# Connector_0_V1_01.net
KiCad netlist of a schematic drawn in Altium Designer
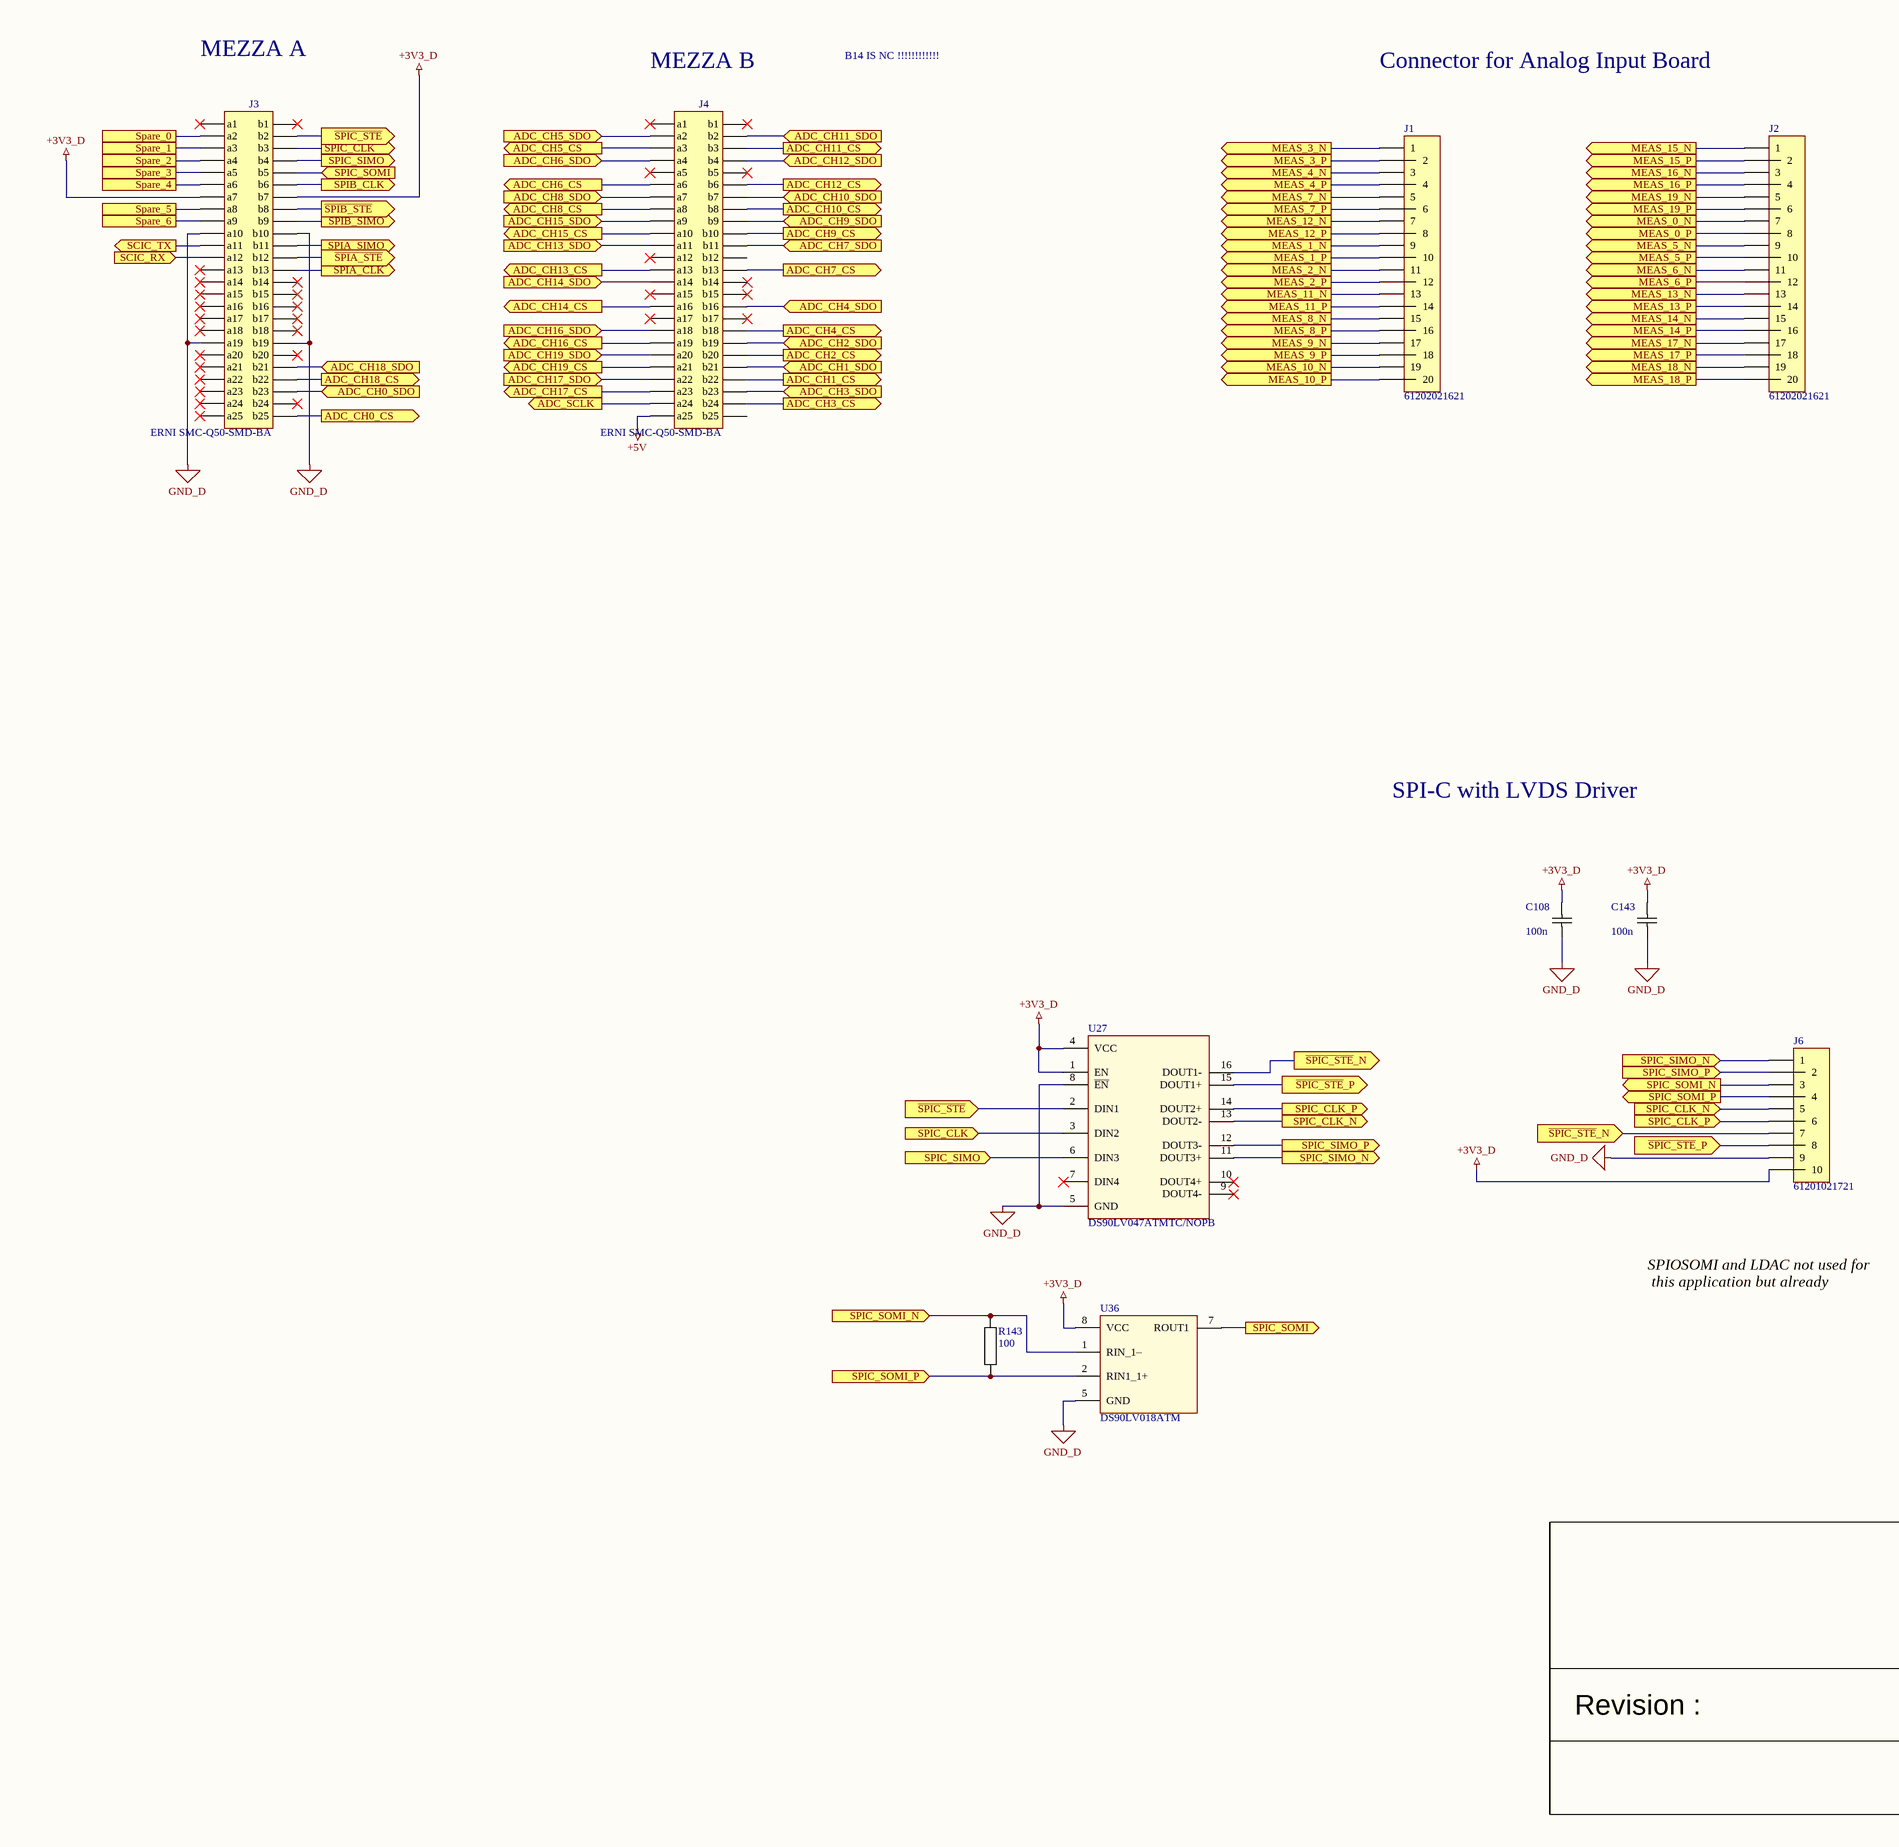
[diagram p0: Connector_0_V1_01.SchDoc, left]
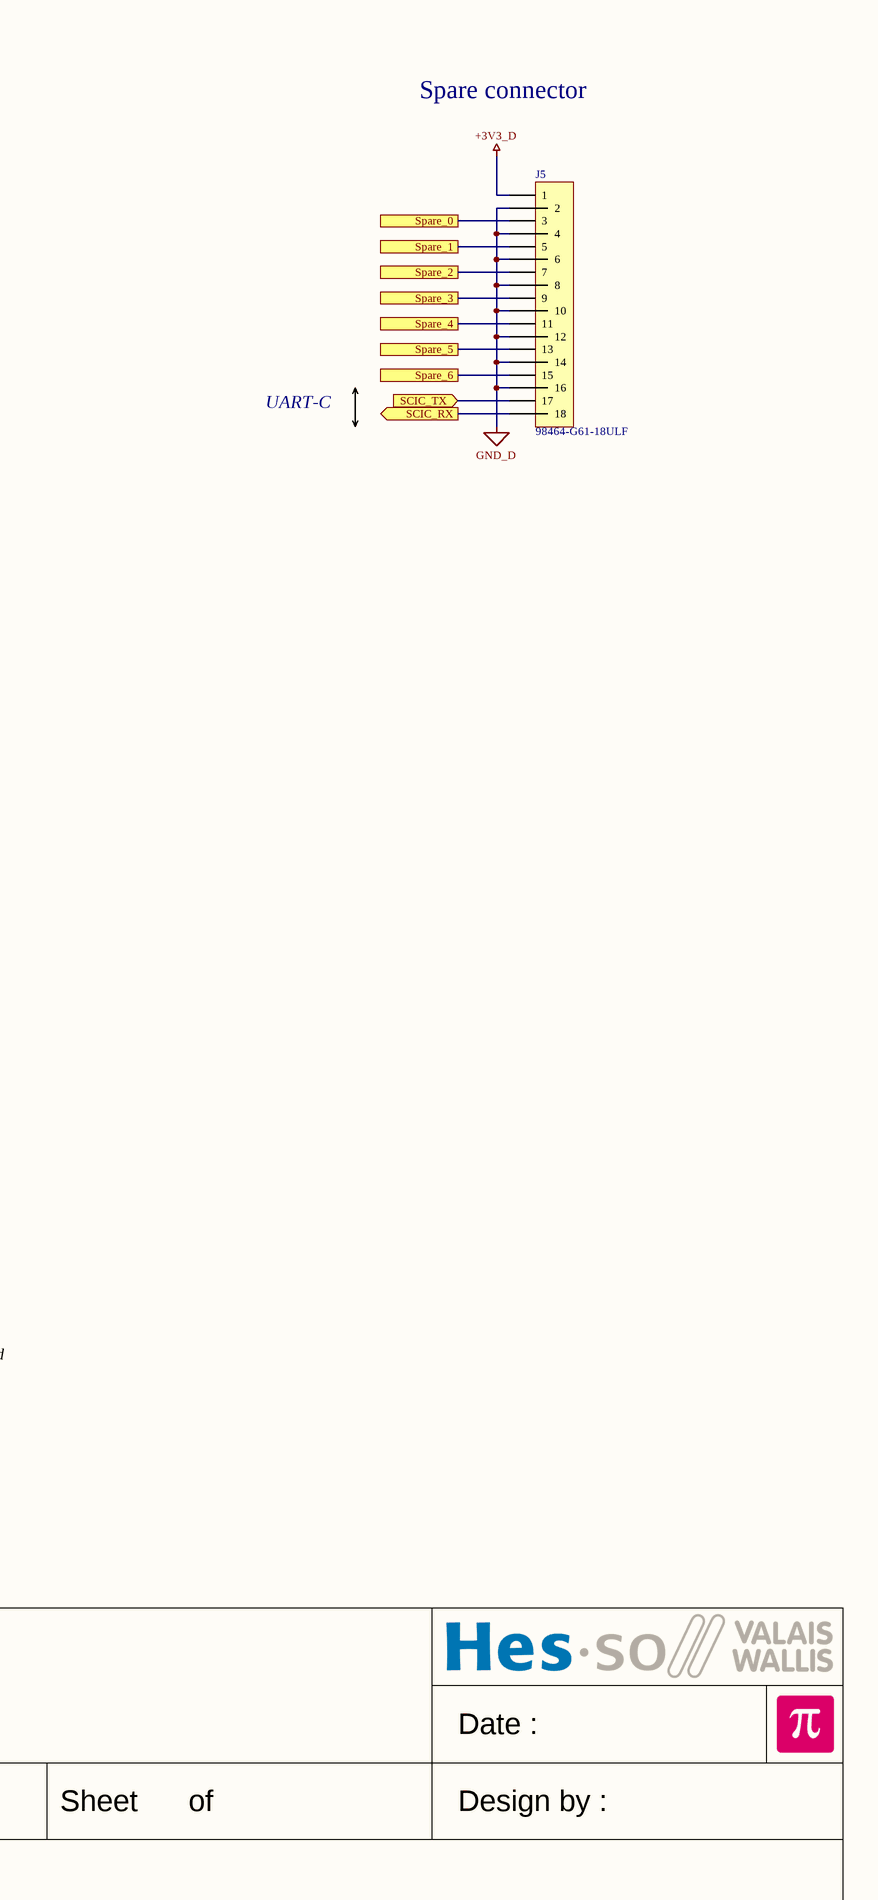
[diagram p1: Connector_0_V1_01.SchDoc, right]

(export (version "E")
  (design (tool "Eeschema 10.0.6"))
  (components
    (comp (ref "C108")
      (value "100n")
      (footprint "CAPACITOR 2012 REFLOW")
      (description "Capacitor X7R 10% 50V 2012(0805)")
      (libsource (lib "Capacitor") (part "Capacitor"))
    )
    (comp (ref "C143")
      (value "100n")
      (footprint "CAPACITOR 2012 REFLOW")
      (description "Capacitor X7R 10% 50V 2012(0805)")
      (libsource (lib "Capacitor") (part "Capacitor"))
    )
    (comp (ref "J1")
      (value "61202021621")
      (footprint "FlatCable2x10 2.54MM RIGHT ANGLE TH")
      (description "FlatCable2x10")
      (fields (field (name "MANUFACTURER") "Wurth Elektronik"))
      (libsource (lib "Connector") (part "FlatCable2x10"))
    )
    (comp (ref "J2")
      (value "61202021621")
      (footprint "FlatCable2x10 2.54MM RIGHT ANGLE TH")
      (description "FlatCable2x10")
      (fields (field (name "MANUFACTURER") "Wurth Elektronik"))
      (libsource (lib "Connector") (part "FlatCable2x10"))
    )
    (comp (ref "J3")
      (value "ERNI SMC-Q50-SMD-BA")
      (footprint "ERNI SMC-Q50-SMD-BA")
      (description "Male 1.27 pitch 2x25 pin connector")
      (libsource (lib "Connector") (part "ERNI SMC-Q50-SMD-BA"))
    )
    (comp (ref "J4")
      (value "ERNI SMC-Q50-SMD-BA")
      (footprint "ERNI SMC-Q50-SMD-BA")
      (description "Male 1.27 pitch 2x25 pin connector")
      (libsource (lib "Connector") (part "ERNI SMC-Q50-SMD-BA"))
    )
    (comp (ref "J5")
      (value "98464-G61-18ULF")
      (footprint "FlatCable2x9 2MM Straight SMD FCI 98414-G52-18ALF")
      (description "FlatCable2x9")
      (fields (field (name "MANUFACTURER") "Amphenol FCI"))
      (libsource (lib "Connector") (part "FlatCable2x9"))
    )
    (comp (ref "J6")
      (value "61201021721")
      (footprint "FlatCable2x5 2.54MM Straight TH")
      (description "FlatCable2x5")
      (fields (field (name "MANUFACTURER") "Wurth Elektronik"))
      (libsource (lib "Connector") (part "FlatCable2x5"))
    )
    (comp (ref "R143")
      (value "100")
      (footprint "RESISTOR 1608 REFLOW")
      (description "Resistor 1% 50V 100mW 1608(0603)")
      (libsource (lib "Resistor") (part "Resistor"))
    )
    (comp (ref "U27")
      (value "DS90LV047ATMTC/NOPB")
      (footprint "TSSOP16 P0.65 C5.0x4.5 H1.1")
      (description "DS90LV047A 3-V LVDS Quad CMOS Differential Line Driver")
      (fields (field (name "MANUFACTURER") "Texas Instruments"))
      (libsource (lib "IntegratedCircuit") (part "DS90LV047A"))
    )
    (comp (ref "U36")
      (value "DS90LV018ATM")
      (footprint "SO8 P1.27 C4.0X5.0 H1.75")
      (description "3-V LVDS single CMOS differential line receiver")
      (libsource (lib "IntegratedCircuit") (part "DS90LV018ATM"))
    )
  )
  (nets
    (net (code "1") (name "+3V3_D") (class "Default")
      (node (ref "C108") (pin "2") (pinfunction "2_2") (pintype "passive"))
      (node (ref "C143") (pin "2") (pinfunction "2_2") (pintype "passive"))
      (node (ref "J3") (pin "a7") (pinfunction "a7_a7") (pintype "passive"))
      (node (ref "J3") (pin "b7") (pinfunction "b7_b7") (pintype "passive"))
      (node (ref "J5") (pin "1") (pinfunction "1_1") (pintype "passive"))
      (node (ref "J6") (pin "10") (pinfunction "10_10") (pintype "passive"))
      (node (ref "U27") (pin "1") (pinfunction "EN_1") (pintype "passive"))
      (node (ref "U27") (pin "4") (pinfunction "VCC_4") (pintype "passive"))
      (node (ref "U36") (pin "8") (pinfunction "VCC_8") (pintype "passive"))
    )
    (net (code "2") (name "+5V") (class "Default")
      (node (ref "J4") (pin "a25") (pinfunction "a25_a25") (pintype "passive"))
    )
    (net (code "3") (name "/ADC_CH0_CS") (class "Default")
      (node (ref "J3") (pin "b25") (pinfunction "b25_b25") (pintype "passive"))
    )
    (net (code "4") (name "/ADC_CH0_SDO") (class "Default")
      (node (ref "J3") (pin "b23") (pinfunction "b23_b23") (pintype "passive"))
    )
    (net (code "5") (name "/ADC_CH1_CS") (class "Default")
      (node (ref "J4") (pin "b22") (pinfunction "b22_b22") (pintype "passive"))
    )
    (net (code "6") (name "/ADC_CH1_SDO") (class "Default")
      (node (ref "J4") (pin "b21") (pinfunction "b21_b21") (pintype "passive"))
    )
    (net (code "7") (name "/ADC_CH2_CS") (class "Default")
      (node (ref "J4") (pin "b20") (pinfunction "b20_b20") (pintype "passive"))
    )
    (net (code "8") (name "/ADC_CH2_SDO") (class "Default")
      (node (ref "J4") (pin "b19") (pinfunction "b19_b19") (pintype "passive"))
    )
    (net (code "9") (name "/ADC_CH3_CS") (class "Default")
      (node (ref "J4") (pin "b24") (pinfunction "b24_b24") (pintype "passive"))
    )
    (net (code "10") (name "/ADC_CH3_SDO") (class "Default")
      (node (ref "J4") (pin "b23") (pinfunction "b23_b23") (pintype "passive"))
    )
    (net (code "11") (name "/ADC_CH4_CS") (class "Default")
      (node (ref "J4") (pin "b18") (pinfunction "b18_b18") (pintype "passive"))
    )
    (net (code "12") (name "/ADC_CH4_SDO") (class "Default")
      (node (ref "J4") (pin "b16") (pinfunction "b16_b16") (pintype "passive"))
    )
    (net (code "13") (name "/ADC_CH5_CS") (class "Default")
      (node (ref "J4") (pin "a3") (pinfunction "a3_a3") (pintype "passive"))
    )
    (net (code "14") (name "/ADC_CH5_SDO") (class "Default")
      (node (ref "J4") (pin "a2") (pinfunction "a2_a2") (pintype "passive"))
    )
    (net (code "15") (name "/ADC_CH6_CS") (class "Default")
      (node (ref "J4") (pin "a6") (pinfunction "a6_a6") (pintype "passive"))
    )
    (net (code "16") (name "/ADC_CH6_SDO") (class "Default")
      (node (ref "J4") (pin "a4") (pinfunction "a4_a4") (pintype "passive"))
    )
    (net (code "17") (name "/ADC_CH7_CS") (class "Default")
      (node (ref "J4") (pin "b13") (pinfunction "b13_b13") (pintype "passive"))
    )
    (net (code "18") (name "/ADC_CH7_SDO") (class "Default")
      (node (ref "J4") (pin "b11") (pinfunction "b11_b11") (pintype "passive"))
    )
    (net (code "19") (name "/ADC_CH8_CS") (class "Default")
      (node (ref "J4") (pin "a8") (pinfunction "a8_a8") (pintype "passive"))
    )
    (net (code "20") (name "/ADC_CH8_SDO") (class "Default")
      (node (ref "J4") (pin "a7") (pinfunction "a7_a7") (pintype "passive"))
    )
    (net (code "21") (name "/ADC_CH9_CS") (class "Default")
      (node (ref "J4") (pin "b10") (pinfunction "b10_b10") (pintype "passive"))
    )
    (net (code "22") (name "/ADC_CH9_SDO") (class "Default")
      (node (ref "J4") (pin "b9") (pinfunction "b9_b9") (pintype "passive"))
    )
    (net (code "23") (name "/ADC_CH10_CS") (class "Default")
      (node (ref "J4") (pin "b8") (pinfunction "b8_b8") (pintype "passive"))
    )
    (net (code "24") (name "/ADC_CH10_SDO") (class "Default")
      (node (ref "J4") (pin "b7") (pinfunction "b7_b7") (pintype "passive"))
    )
    (net (code "25") (name "/ADC_CH11_CS") (class "Default")
      (node (ref "J4") (pin "b3") (pinfunction "b3_b3") (pintype "passive"))
    )
    (net (code "26") (name "/ADC_CH11_SDO") (class "Default")
      (node (ref "J4") (pin "b2") (pinfunction "b2_b2") (pintype "passive"))
    )
    (net (code "27") (name "/ADC_CH12_CS") (class "Default")
      (node (ref "J4") (pin "b6") (pinfunction "b6_b6") (pintype "passive"))
    )
    (net (code "28") (name "/ADC_CH12_SDO") (class "Default")
      (node (ref "J4") (pin "b4") (pinfunction "b4_b4") (pintype "passive"))
    )
    (net (code "29") (name "/ADC_CH13_CS") (class "Default")
      (node (ref "J4") (pin "a13") (pinfunction "a13_a13") (pintype "passive"))
    )
    (net (code "30") (name "/ADC_CH13_SDO") (class "Default")
      (node (ref "J4") (pin "a11") (pinfunction "a11_a11") (pintype "passive"))
    )
    (net (code "31") (name "/ADC_CH14_CS") (class "Default")
      (node (ref "J4") (pin "a16") (pinfunction "a16_a16") (pintype "passive"))
    )
    (net (code "32") (name "/ADC_CH14_SDO") (class "Default")
      (node (ref "J4") (pin "a14") (pinfunction "a14_a14") (pintype "passive"))
    )
    (net (code "33") (name "/ADC_CH15_CS") (class "Default")
      (node (ref "J4") (pin "a10") (pinfunction "a10_a10") (pintype "passive"))
    )
    (net (code "34") (name "/ADC_CH15_SDO") (class "Default")
      (node (ref "J4") (pin "a9") (pinfunction "a9_a9") (pintype "passive"))
    )
    (net (code "35") (name "/ADC_CH16_CS") (class "Default")
      (node (ref "J4") (pin "a19") (pinfunction "a19_a19") (pintype "passive"))
    )
    (net (code "36") (name "/ADC_CH16_SDO") (class "Default")
      (node (ref "J4") (pin "a18") (pinfunction "a18_a18") (pintype "passive"))
    )
    (net (code "37") (name "/ADC_CH17_CS") (class "Default")
      (node (ref "J4") (pin "a23") (pinfunction "a23_a23") (pintype "passive"))
    )
    (net (code "38") (name "/ADC_CH17_SDO") (class "Default")
      (node (ref "J4") (pin "a22") (pinfunction "a22_a22") (pintype "passive"))
    )
    (net (code "39") (name "/ADC_CH18_CS") (class "Default")
      (node (ref "J3") (pin "b22") (pinfunction "b22_b22") (pintype "passive"))
    )
    (net (code "40") (name "/ADC_CH18_SDO") (class "Default")
      (node (ref "J3") (pin "b21") (pinfunction "b21_b21") (pintype "passive"))
    )
    (net (code "41") (name "/ADC_CH19_CS") (class "Default")
      (node (ref "J4") (pin "a21") (pinfunction "a21_a21") (pintype "passive"))
    )
    (net (code "42") (name "/ADC_CH19_SDO") (class "Default")
      (node (ref "J4") (pin "a20") (pinfunction "a20_a20") (pintype "passive"))
    )
    (net (code "43") (name "/ADC_SCLK") (class "Default")
      (node (ref "J4") (pin "a24") (pinfunction "a24_a24") (pintype "passive"))
    )
    (net (code "44") (name "/MEAS_0_N") (class "Default")
      (node (ref "J2") (pin "7") (pinfunction "7_7") (pintype "passive"))
    )
    (net (code "45") (name "/MEAS_0_P") (class "Default")
      (node (ref "J2") (pin "8") (pinfunction "8_8") (pintype "passive"))
    )
    (net (code "46") (name "/MEAS_1_N") (class "Default")
      (node (ref "J1") (pin "9") (pinfunction "9_9") (pintype "passive"))
    )
    (net (code "47") (name "/MEAS_1_P") (class "Default")
      (node (ref "J1") (pin "10") (pinfunction "10_10") (pintype "passive"))
    )
    (net (code "48") (name "/MEAS_2_N") (class "Default")
      (node (ref "J1") (pin "11") (pinfunction "11_11") (pintype "passive"))
    )
    (net (code "49") (name "/MEAS_2_P") (class "Default")
      (node (ref "J1") (pin "12") (pinfunction "12_12") (pintype "passive"))
    )
    (net (code "50") (name "/MEAS_3_N") (class "Default")
      (node (ref "J1") (pin "1") (pinfunction "1_1") (pintype "passive"))
    )
    (net (code "51") (name "/MEAS_3_P") (class "Default")
      (node (ref "J1") (pin "2") (pinfunction "2_2") (pintype "passive"))
    )
    (net (code "52") (name "/MEAS_4_N") (class "Default")
      (node (ref "J1") (pin "3") (pinfunction "3_3") (pintype "passive"))
    )
    (net (code "53") (name "/MEAS_4_P") (class "Default")
      (node (ref "J1") (pin "4") (pinfunction "4_4") (pintype "passive"))
    )
    (net (code "54") (name "/MEAS_5_N") (class "Default")
      (node (ref "J2") (pin "9") (pinfunction "9_9") (pintype "passive"))
    )
    (net (code "55") (name "/MEAS_5_P") (class "Default")
      (node (ref "J2") (pin "10") (pinfunction "10_10") (pintype "passive"))
    )
    (net (code "56") (name "/MEAS_6_N") (class "Default")
      (node (ref "J2") (pin "11") (pinfunction "11_11") (pintype "passive"))
    )
    (net (code "57") (name "/MEAS_6_P") (class "Default")
      (node (ref "J2") (pin "12") (pinfunction "12_12") (pintype "passive"))
    )
    (net (code "58") (name "/MEAS_7_N") (class "Default")
      (node (ref "J1") (pin "5") (pinfunction "5_5") (pintype "passive"))
    )
    (net (code "59") (name "/MEAS_7_P") (class "Default")
      (node (ref "J1") (pin "6") (pinfunction "6_6") (pintype "passive"))
    )
    (net (code "60") (name "/MEAS_8_N") (class "Default")
      (node (ref "J1") (pin "15") (pinfunction "15_15") (pintype "passive"))
    )
    (net (code "61") (name "/MEAS_8_P") (class "Default")
      (node (ref "J1") (pin "16") (pinfunction "16_16") (pintype "passive"))
    )
    (net (code "62") (name "/MEAS_9_N") (class "Default")
      (node (ref "J1") (pin "17") (pinfunction "17_17") (pintype "passive"))
    )
    (net (code "63") (name "/MEAS_9_P") (class "Default")
      (node (ref "J1") (pin "18") (pinfunction "18_18") (pintype "passive"))
    )
    (net (code "64") (name "/MEAS_10_N") (class "Default")
      (node (ref "J1") (pin "19") (pinfunction "19_19") (pintype "passive"))
    )
    (net (code "65") (name "/MEAS_10_P") (class "Default")
      (node (ref "J1") (pin "20") (pinfunction "20_20") (pintype "passive"))
    )
    (net (code "66") (name "/MEAS_11_N") (class "Default")
      (node (ref "J1") (pin "13") (pinfunction "13_13") (pintype "passive"))
    )
    (net (code "67") (name "/MEAS_11_P") (class "Default")
      (node (ref "J1") (pin "14") (pinfunction "14_14") (pintype "passive"))
    )
    (net (code "68") (name "/MEAS_12_N") (class "Default")
      (node (ref "J1") (pin "7") (pinfunction "7_7") (pintype "passive"))
    )
    (net (code "69") (name "/MEAS_12_P") (class "Default")
      (node (ref "J1") (pin "8") (pinfunction "8_8") (pintype "passive"))
    )
    (net (code "70") (name "/MEAS_13_N") (class "Default")
      (node (ref "J2") (pin "13") (pinfunction "13_13") (pintype "passive"))
    )
    (net (code "71") (name "/MEAS_13_P") (class "Default")
      (node (ref "J2") (pin "14") (pinfunction "14_14") (pintype "passive"))
    )
    (net (code "72") (name "/MEAS_14_N") (class "Default")
      (node (ref "J2") (pin "15") (pinfunction "15_15") (pintype "passive"))
    )
    (net (code "73") (name "/MEAS_14_P") (class "Default")
      (node (ref "J2") (pin "16") (pinfunction "16_16") (pintype "passive"))
    )
    (net (code "74") (name "/MEAS_15_N") (class "Default")
      (node (ref "J2") (pin "1") (pinfunction "1_1") (pintype "passive"))
    )
    (net (code "75") (name "/MEAS_15_P") (class "Default")
      (node (ref "J2") (pin "2") (pinfunction "2_2") (pintype "passive"))
    )
    (net (code "76") (name "/MEAS_16_N") (class "Default")
      (node (ref "J2") (pin "3") (pinfunction "3_3") (pintype "passive"))
    )
    (net (code "77") (name "/MEAS_16_P") (class "Default")
      (node (ref "J2") (pin "4") (pinfunction "4_4") (pintype "passive"))
    )
    (net (code "78") (name "/MEAS_17_N") (class "Default")
      (node (ref "J2") (pin "17") (pinfunction "17_17") (pintype "passive"))
    )
    (net (code "79") (name "/MEAS_17_P") (class "Default")
      (node (ref "J2") (pin "18") (pinfunction "18_18") (pintype "passive"))
    )
    (net (code "80") (name "/MEAS_18_N") (class "Default")
      (node (ref "J2") (pin "19") (pinfunction "19_19") (pintype "passive"))
    )
    (net (code "81") (name "/MEAS_18_P") (class "Default")
      (node (ref "J2") (pin "20") (pinfunction "20_20") (pintype "passive"))
    )
    (net (code "82") (name "/MEAS_19_N") (class "Default")
      (node (ref "J2") (pin "5") (pinfunction "5_5") (pintype "passive"))
    )
    (net (code "83") (name "/MEAS_19_P") (class "Default")
      (node (ref "J2") (pin "6") (pinfunction "6_6") (pintype "passive"))
    )
    (net (code "84") (name "/SCIC_RX") (class "Default")
      (node (ref "J3") (pin "a12") (pinfunction "a12_a12") (pintype "passive"))
      (node (ref "J5") (pin "18") (pinfunction "18_18") (pintype "passive"))
    )
    (net (code "85") (name "/SCIC_TX") (class "Default")
      (node (ref "J3") (pin "a11") (pinfunction "a11_a11") (pintype "passive"))
      (node (ref "J5") (pin "17") (pinfunction "17_17") (pintype "passive"))
    )
    (net (code "86") (name "/SPIA_CLK") (class "Default")
      (node (ref "J3") (pin "b13") (pinfunction "b13_b13") (pintype "passive"))
    )
    (net (code "87") (name "/SPIA_SIMO") (class "Default")
      (node (ref "J3") (pin "b11") (pinfunction "b11_b11") (pintype "passive"))
    )
    (net (code "88") (name "/SPIB_CLK") (class "Default")
      (node (ref "J3") (pin "b6") (pinfunction "b6_b6") (pintype "passive"))
    )
    (net (code "89") (name "/SPIB_SIMO") (class "Default")
      (node (ref "J3") (pin "b9") (pinfunction "b9_b9") (pintype "passive"))
    )
    (net (code "90") (name "/SPIC_CLK") (class "Default")
      (node (ref "J3") (pin "b3") (pinfunction "b3_b3") (pintype "passive"))
      (node (ref "U27") (pin "3") (pinfunction "DIN2_3") (pintype "passive"))
    )
    (net (code "91") (name "/SPIC_CLK_N") (class "Default")
      (node (ref "J6") (pin "5") (pinfunction "5_5") (pintype "passive"))
      (node (ref "U27") (pin "13") (pinfunction "DOUT2-_13") (pintype "passive"))
    )
    (net (code "92") (name "/SPIC_CLK_P") (class "Default")
      (node (ref "J6") (pin "6") (pinfunction "6_6") (pintype "passive"))
      (node (ref "U27") (pin "14") (pinfunction "DOUT2+_14") (pintype "passive"))
    )
    (net (code "93") (name "/SPIC_SIMO") (class "Default")
      (node (ref "J3") (pin "b4") (pinfunction "b4_b4") (pintype "passive"))
      (node (ref "U27") (pin "6") (pinfunction "DIN3_6") (pintype "passive"))
    )
    (net (code "94") (name "/SPIC_SIMO_N") (class "Default")
      (node (ref "J6") (pin "1") (pinfunction "1_1") (pintype "passive"))
      (node (ref "U27") (pin "11") (pinfunction "DOUT3+_11") (pintype "passive"))
    )
    (net (code "95") (name "/SPIC_SIMO_P") (class "Default")
      (node (ref "J6") (pin "2") (pinfunction "2_2") (pintype "passive"))
      (node (ref "U27") (pin "12") (pinfunction "DOUT3-_12") (pintype "passive"))
    )
    (net (code "96") (name "/SPIC_SOMI") (class "Default")
      (node (ref "J3") (pin "b5") (pinfunction "b5_b5") (pintype "passive"))
      (node (ref "U36") (pin "7") (pinfunction "ROUT1_7") (pintype "passive"))
    )
    (net (code "97") (name "/SPIC_SOMI_N") (class "Default")
      (node (ref "J6") (pin "3") (pinfunction "3_3") (pintype "passive"))
      (node (ref "R143") (pin "1") (pinfunction "1_1") (pintype "passive"))
      (node (ref "U36") (pin "1") (pinfunction "RIN_1–_1") (pintype "passive"))
    )
    (net (code "98") (name "/SPIC_SOMI_P") (class "Default")
      (node (ref "J6") (pin "4") (pinfunction "4_4") (pintype "passive"))
      (node (ref "R143") (pin "2") (pinfunction "2_2") (pintype "passive"))
      (node (ref "U36") (pin "2") (pinfunction "RIN1_1+_2") (pintype "passive"))
    )
    (net (code "99") (name "/Spare_0") (class "Default")
      (node (ref "J3") (pin "a2") (pinfunction "a2_a2") (pintype "passive"))
      (node (ref "J5") (pin "3") (pinfunction "3_3") (pintype "passive"))
    )
    (net (code "100") (name "/Spare_1") (class "Default")
      (node (ref "J3") (pin "a3") (pinfunction "a3_a3") (pintype "passive"))
      (node (ref "J5") (pin "5") (pinfunction "5_5") (pintype "passive"))
    )
    (net (code "101") (name "/Spare_2") (class "Default")
      (node (ref "J3") (pin "a4") (pinfunction "a4_a4") (pintype "passive"))
      (node (ref "J5") (pin "7") (pinfunction "7_7") (pintype "passive"))
    )
    (net (code "102") (name "/Spare_3") (class "Default")
      (node (ref "J3") (pin "a5") (pinfunction "a5_a5") (pintype "passive"))
      (node (ref "J5") (pin "9") (pinfunction "9_9") (pintype "passive"))
    )
    (net (code "103") (name "/Spare_4") (class "Default")
      (node (ref "J3") (pin "a6") (pinfunction "a6_a6") (pintype "passive"))
      (node (ref "J5") (pin "11") (pinfunction "11_11") (pintype "passive"))
    )
    (net (code "104") (name "/Spare_5") (class "Default")
      (node (ref "J3") (pin "a8") (pinfunction "a8_a8") (pintype "passive"))
      (node (ref "J5") (pin "13") (pinfunction "13_13") (pintype "passive"))
    )
    (net (code "105") (name "/Spare_6") (class "Default")
      (node (ref "J3") (pin "a9") (pinfunction "a9_a9") (pintype "passive"))
      (node (ref "J5") (pin "15") (pinfunction "15_15") (pintype "passive"))
    )
    (net (code "106") (name "/~{SPIA_STE}") (class "Default")
      (node (ref "J3") (pin "b12") (pinfunction "b12_b12") (pintype "passive"))
    )
    (net (code "107") (name "/~{SPIB_STE}") (class "Default")
      (node (ref "J3") (pin "b8") (pinfunction "b8_b8") (pintype "passive"))
    )
    (net (code "108") (name "/~{SPIC_STE}") (class "Default")
      (node (ref "J3") (pin "b2") (pinfunction "b2_b2") (pintype "passive"))
      (node (ref "U27") (pin "2") (pinfunction "DIN1_2") (pintype "passive"))
    )
    (net (code "109") (name "/~{SPIC_STE}_N") (class "Default")
      (node (ref "J6") (pin "7") (pinfunction "7_7") (pintype "passive"))
      (node (ref "U27") (pin "16") (pinfunction "DOUT1-_16") (pintype "passive"))
    )
    (net (code "110") (name "/~{SPIC_STE}_P") (class "Default")
      (node (ref "J6") (pin "8") (pinfunction "8_8") (pintype "passive"))
      (node (ref "U27") (pin "15") (pinfunction "DOUT1+_15") (pintype "passive"))
    )
    (net (code "111") (name "GND_D") (class "Default")
      (node (ref "C108") (pin "1") (pinfunction "1_1") (pintype "passive"))
      (node (ref "C143") (pin "1") (pinfunction "1_1") (pintype "passive"))
      (node (ref "J3") (pin "a10") (pinfunction "a10_a10") (pintype "passive"))
      (node (ref "J3") (pin "a19") (pinfunction "a19_a19") (pintype "passive"))
      (node (ref "J3") (pin "b10") (pinfunction "b10_b10") (pintype "passive"))
      (node (ref "J3") (pin "b19") (pinfunction "b19_b19") (pintype "passive"))
      (node (ref "J5") (pin "10") (pinfunction "10_10") (pintype "passive"))
      (node (ref "J5") (pin "12") (pinfunction "12_12") (pintype "passive"))
      (node (ref "J5") (pin "14") (pinfunction "14_14") (pintype "passive"))
      (node (ref "J5") (pin "16") (pinfunction "16_16") (pintype "passive"))
      (node (ref "J5") (pin "2") (pinfunction "2_2") (pintype "passive"))
      (node (ref "J5") (pin "4") (pinfunction "4_4") (pintype "passive"))
      (node (ref "J5") (pin "6") (pinfunction "6_6") (pintype "passive"))
      (node (ref "J5") (pin "8") (pinfunction "8_8") (pintype "passive"))
      (node (ref "J6") (pin "9") (pinfunction "9_9") (pintype "passive"))
      (node (ref "U27") (pin "5") (pinfunction "GND_5") (pintype "passive"))
      (node (ref "U27") (pin "8") (pinfunction "~{EN}_8") (pintype "passive"))
      (node (ref "U36") (pin "5") (pinfunction "GND_5") (pintype "passive"))
    )
    (net (code "112") (name "unconnected-(J3-Pada1)") (class "Default")
      (node (ref "J3") (pin "a1") (pinfunction "a1_a1") (pintype "passive+no_connect"))
    )
    (net (code "113") (name "unconnected-(J3-Pada13)") (class "Default")
      (node (ref "J3") (pin "a13") (pinfunction "a13_a13") (pintype "passive+no_connect"))
    )
    (net (code "114") (name "unconnected-(J3-Pada14)") (class "Default")
      (node (ref "J3") (pin "a14") (pinfunction "a14_a14") (pintype "passive+no_connect"))
    )
    (net (code "115") (name "unconnected-(J3-Pada15)") (class "Default")
      (node (ref "J3") (pin "a15") (pinfunction "a15_a15") (pintype "passive+no_connect"))
    )
    (net (code "116") (name "unconnected-(J3-Pada16)") (class "Default")
      (node (ref "J3") (pin "a16") (pinfunction "a16_a16") (pintype "passive+no_connect"))
    )
    (net (code "117") (name "unconnected-(J3-Pada17)") (class "Default")
      (node (ref "J3") (pin "a17") (pinfunction "a17_a17") (pintype "passive+no_connect"))
    )
    (net (code "118") (name "unconnected-(J3-Pada18)") (class "Default")
      (node (ref "J3") (pin "a18") (pinfunction "a18_a18") (pintype "passive+no_connect"))
    )
    (net (code "119") (name "unconnected-(J3-Pada20)") (class "Default")
      (node (ref "J3") (pin "a20") (pinfunction "a20_a20") (pintype "passive+no_connect"))
    )
    (net (code "120") (name "unconnected-(J3-Pada21)") (class "Default")
      (node (ref "J3") (pin "a21") (pinfunction "a21_a21") (pintype "passive+no_connect"))
    )
    (net (code "121") (name "unconnected-(J3-Pada22)") (class "Default")
      (node (ref "J3") (pin "a22") (pinfunction "a22_a22") (pintype "passive+no_connect"))
    )
    (net (code "122") (name "unconnected-(J3-Pada23)") (class "Default")
      (node (ref "J3") (pin "a23") (pinfunction "a23_a23") (pintype "passive+no_connect"))
    )
    (net (code "123") (name "unconnected-(J3-Pada24)") (class "Default")
      (node (ref "J3") (pin "a24") (pinfunction "a24_a24") (pintype "passive+no_connect"))
    )
    (net (code "124") (name "unconnected-(J3-Pada25)") (class "Default")
      (node (ref "J3") (pin "a25") (pinfunction "a25_a25") (pintype "passive+no_connect"))
    )
    (net (code "125") (name "unconnected-(J3-Padb1)") (class "Default")
      (node (ref "J3") (pin "b1") (pinfunction "b1_b1") (pintype "passive+no_connect"))
    )
    (net (code "126") (name "unconnected-(J3-Padb14)") (class "Default")
      (node (ref "J3") (pin "b14") (pinfunction "b14_b14") (pintype "passive+no_connect"))
    )
    (net (code "127") (name "unconnected-(J3-Padb15)") (class "Default")
      (node (ref "J3") (pin "b15") (pinfunction "b15_b15") (pintype "passive+no_connect"))
    )
    (net (code "128") (name "unconnected-(J3-Padb16)") (class "Default")
      (node (ref "J3") (pin "b16") (pinfunction "b16_b16") (pintype "passive+no_connect"))
    )
    (net (code "129") (name "unconnected-(J3-Padb17)") (class "Default")
      (node (ref "J3") (pin "b17") (pinfunction "b17_b17") (pintype "passive+no_connect"))
    )
    (net (code "130") (name "unconnected-(J3-Padb18)") (class "Default")
      (node (ref "J3") (pin "b18") (pinfunction "b18_b18") (pintype "passive+no_connect"))
    )
    (net (code "131") (name "unconnected-(J3-Padb20)") (class "Default")
      (node (ref "J3") (pin "b20") (pinfunction "b20_b20") (pintype "passive+no_connect"))
    )
    (net (code "132") (name "unconnected-(J3-Padb24)") (class "Default")
      (node (ref "J3") (pin "b24") (pinfunction "b24_b24") (pintype "passive+no_connect"))
    )
    (net (code "133") (name "unconnected-(J4-Pada1)") (class "Default")
      (node (ref "J4") (pin "a1") (pinfunction "a1_a1") (pintype "passive+no_connect"))
    )
    (net (code "134") (name "unconnected-(J4-Pada5)") (class "Default")
      (node (ref "J4") (pin "a5") (pinfunction "a5_a5") (pintype "passive+no_connect"))
    )
    (net (code "135") (name "unconnected-(J4-Pada12)") (class "Default")
      (node (ref "J4") (pin "a12") (pinfunction "a12_a12") (pintype "passive+no_connect"))
    )
    (net (code "136") (name "unconnected-(J4-Pada15)") (class "Default")
      (node (ref "J4") (pin "a15") (pinfunction "a15_a15") (pintype "passive+no_connect"))
    )
    (net (code "137") (name "unconnected-(J4-Pada17)") (class "Default")
      (node (ref "J4") (pin "a17") (pinfunction "a17_a17") (pintype "passive+no_connect"))
    )
    (net (code "138") (name "unconnected-(J4-Padb1)") (class "Default")
      (node (ref "J4") (pin "b1") (pinfunction "b1_b1") (pintype "passive+no_connect"))
    )
    (net (code "139") (name "unconnected-(J4-Padb5)") (class "Default")
      (node (ref "J4") (pin "b5") (pinfunction "b5_b5") (pintype "passive+no_connect"))
    )
    (net (code "140") (name "unconnected-(J4-Padb12)") (class "Default")
      (node (ref "J4") (pin "b12") (pinfunction "b12_b12") (pintype "passive"))
    )
    (net (code "141") (name "unconnected-(J4-Padb14)") (class "Default")
      (node (ref "J4") (pin "b14") (pinfunction "b14_b14") (pintype "passive+no_connect"))
    )
    (net (code "142") (name "unconnected-(J4-Padb15)") (class "Default")
      (node (ref "J4") (pin "b15") (pinfunction "b15_b15") (pintype "passive+no_connect"))
    )
    (net (code "143") (name "unconnected-(J4-Padb17)") (class "Default")
      (node (ref "J4") (pin "b17") (pinfunction "b17_b17") (pintype "passive+no_connect"))
    )
    (net (code "144") (name "unconnected-(J4-Padb25)") (class "Default")
      (node (ref "J4") (pin "b25") (pinfunction "b25_b25") (pintype "passive"))
    )
    (net (code "145") (name "unconnected-(U27-DIN4-Pad7)") (class "Default")
      (node (ref "U27") (pin "7") (pinfunction "DIN4_7") (pintype "passive+no_connect"))
    )
    (net (code "146") (name "unconnected-(U27-DOUT4+-Pad10)") (class "Default")
      (node (ref "U27") (pin "10") (pinfunction "DOUT4+_10") (pintype "passive+no_connect"))
    )
    (net (code "147") (name "unconnected-(U27-DOUT4--Pad9)") (class "Default")
      (node (ref "U27") (pin "9") (pinfunction "DOUT4-_9") (pintype "passive+no_connect"))
    )
  )
)
